# mainboard.net
KiCad netlist of a schematic drawn in Altium Designer
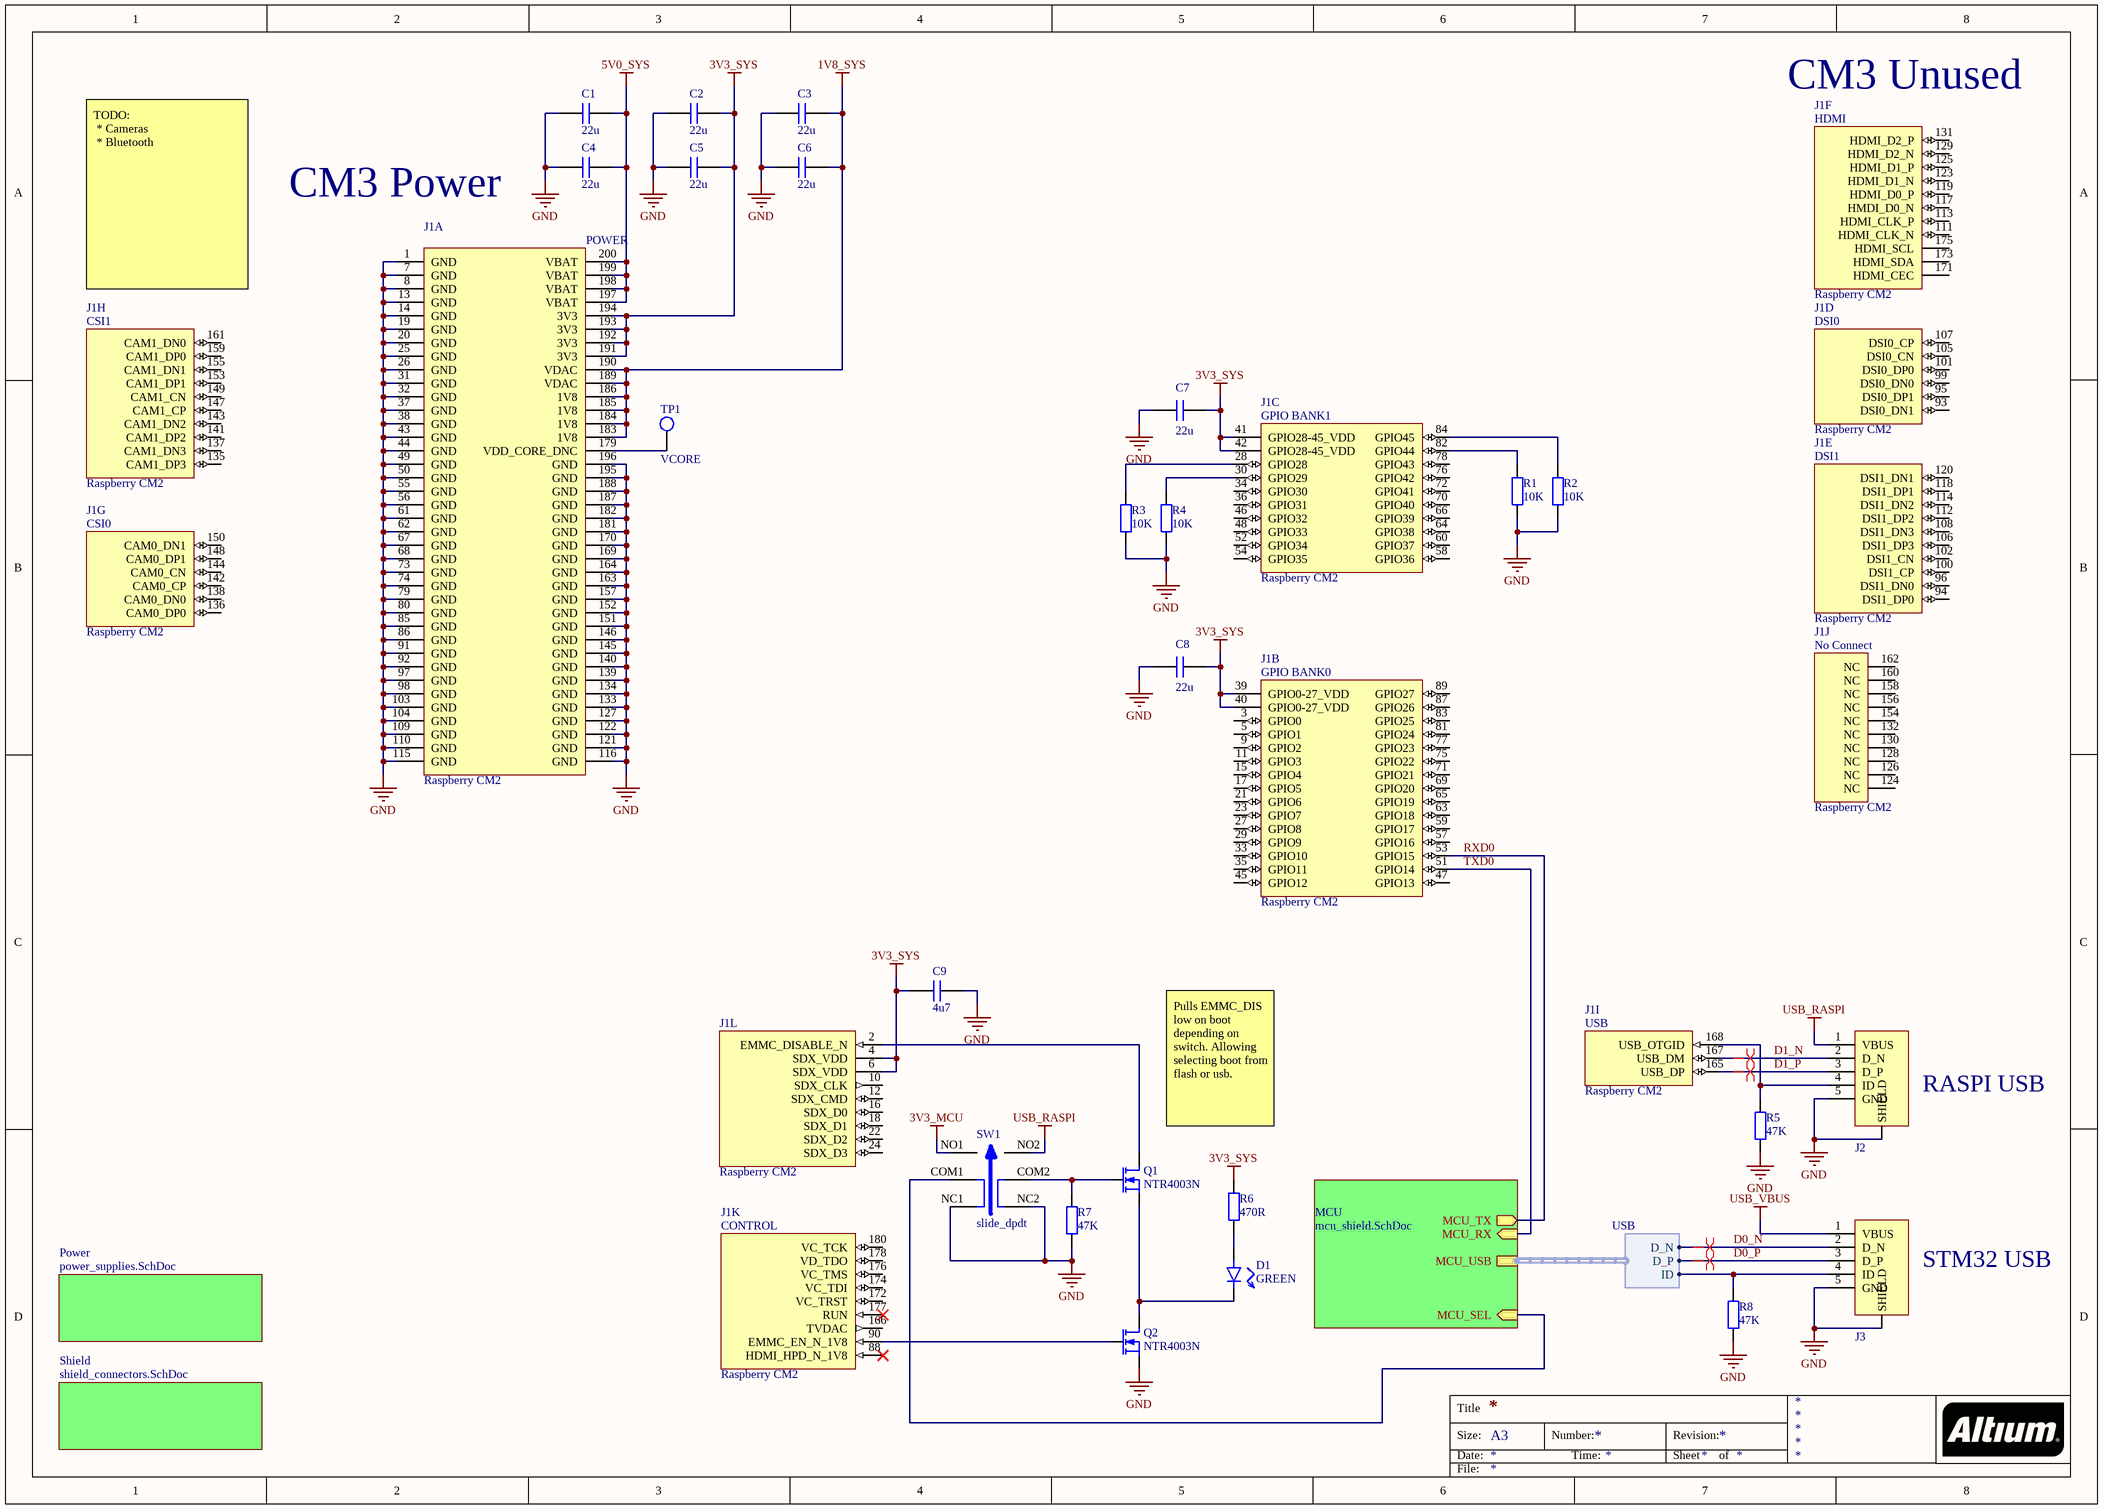
[diagram p0: mainboard.SchDoc]

(export (version "E")
  (design (tool "Eeschema 10.0.6"))
  (components
    (comp (ref "C1")
      (value "22u")
      (footprint "CAPC2012X11N")
      (description "Capacitor")
      (fields (field (name "Comment") "cap"))
      (libsource (lib "lib_passives") (part "cap"))
    )
    (comp (ref "C2")
      (value "22u")
      (footprint "CAPC2012X11N")
      (description "Capacitor")
      (fields (field (name "Comment") "cap"))
      (libsource (lib "lib_passives") (part "cap"))
    )
    (comp (ref "C3")
      (value "22u")
      (footprint "CAPC2012X11N")
      (description "Capacitor")
      (fields (field (name "Comment") "cap"))
      (libsource (lib "lib_passives") (part "cap"))
    )
    (comp (ref "C4")
      (value "22u")
      (footprint "CAPC2012X11N")
      (description "Capacitor")
      (fields (field (name "Comment") "cap"))
      (libsource (lib "lib_passives") (part "cap"))
    )
    (comp (ref "C5")
      (value "22u")
      (footprint "CAPC2012X11N")
      (description "Capacitor")
      (fields (field (name "Comment") "cap"))
      (libsource (lib "lib_passives") (part "cap"))
    )
    (comp (ref "C6")
      (value "22u")
      (footprint "CAPC2012X11N")
      (description "Capacitor")
      (fields (field (name "Comment") "cap"))
      (libsource (lib "lib_passives") (part "cap"))
    )
    (comp (ref "C7")
      (value "22u")
      (footprint "CAPC2012X11N")
      (description "Capacitor")
      (fields (field (name "Comment") "cap"))
      (libsource (lib "lib_passives") (part "cap"))
    )
    (comp (ref "C8")
      (value "22u")
      (footprint "CAPC2012X11N")
      (description "Capacitor")
      (fields (field (name "Comment") "cap"))
      (libsource (lib "lib_passives") (part "cap"))
    )
    (comp (ref "C9")
      (value "4u7")
      (footprint "CAPC1608X08N")
      (description "Capacitor")
      (fields (field (name "Comment") "cap"))
      (libsource (lib "lib_passives") (part "cap"))
    )
    (comp (ref "D1")
      (value "GREEN")
      (footprint "CAPCP1005X06N")
      (description "LED")
      (fields (field (name "Comment") "led"))
      (libsource (lib "lib_actives") (part "led"))
    )
    (comp (ref "J1")
      (value "Raspberry CM2")
      (footprint "raspi_cm3")
      (libsource (lib "lib_raspberry") (part "raspicm2"))
    )
    (comp (ref "J2")
      (value "usb_micro")
      (footprint "usb_micro_10118192-0001LF")
      (description "Micro USB Receptacle")
      (libsource (lib "lib_connectors") (part "usb_micro"))
    )
    (comp (ref "J3")
      (value "usb_micro")
      (footprint "usb_micro_10118192-0001LF")
      (description "Micro USB Receptacle")
      (libsource (lib "lib_connectors") (part "usb_micro"))
    )
    (comp (ref "Q1")
      (value "NTR4003N")
      (footprint "SOT95P235X100-3N")
      (description "N-channel Mosfet")
      (libsource (lib "lib_onsemi") (part "ntr4003n"))
    )
    (comp (ref "Q2")
      (value "NTR4003N")
      (footprint "SOT95P235X100-3N")
      (description "N-channel Mosfet")
      (libsource (lib "lib_onsemi") (part "ntr4003n"))
    )
    (comp (ref "R1")
      (value "10K")
      (footprint "RESC1005X04N")
      (description "Resistor")
      (fields (field (name "Comment") "res"))
      (libsource (lib "lib_passives") (part "res"))
    )
    (comp (ref "R2")
      (value "10K")
      (footprint "RESC1005X04N")
      (description "Resistor")
      (fields (field (name "Comment") "res"))
      (libsource (lib "lib_passives") (part "res"))
    )
    (comp (ref "R3")
      (value "10K")
      (footprint "RESC1005X04N")
      (description "Resistor")
      (fields (field (name "Comment") "res"))
      (libsource (lib "lib_passives") (part "res"))
    )
    (comp (ref "R4")
      (value "10K")
      (footprint "RESC1005X04N")
      (description "Resistor")
      (fields (field (name "Comment") "res"))
      (libsource (lib "lib_passives") (part "res"))
    )
    (comp (ref "R5")
      (value "47K")
      (footprint "RESC1005X04N")
      (description "Resistor")
      (fields (field (name "Comment") "res"))
      (libsource (lib "lib_passives") (part "res"))
    )
    (comp (ref "R6")
      (value "470R")
      (footprint "RESC1005X04N")
      (description "Resistor")
      (fields (field (name "Comment") "res"))
      (libsource (lib "lib_passives") (part "res"))
    )
    (comp (ref "R7")
      (value "47K")
      (footprint "RESC1005X04N")
      (description "Resistor")
      (fields (field (name "Comment") "res"))
      (libsource (lib "") (part "res_1"))
    )
    (comp (ref "R8")
      (value "47K")
      (footprint "RESC1005X04N")
      (description "Resistor")
      (fields (field (name "Comment") "res"))
      (libsource (lib "lib_passives") (part "res"))
    )
    (comp (ref "SW1")
      (value "slide_dpdt")
      (footprint "JS202011SCQN")
      (description "DPDT")
      (libsource (lib "lib_switches") (part "slide_dpdt"))
    )
    (comp (ref "TP1")
      (value "VCORE")
      (footprint "testpoint_smd")
      (description "Test point")
      (libsource (lib "lib_passives") (part "testpoint"))
    )
  )
  (nets
    (net (code "2") (name "/D0_N") (class "Default")
      (node (ref "J3") (pin "2") (pinfunction "D_N_2") (pintype "passive"))
    )
    (net (code "3") (name "/D0_P") (class "Default")
      (node (ref "J3") (pin "3") (pinfunction "D_P_3") (pintype "passive"))
    )
    (net (code "4") (name "/D1_N") (class "Default")
      (node (ref "J1") (pin "167") (pinfunction "USB_DM_167") (pintype "bidirectional"))
      (node (ref "J2") (pin "2") (pinfunction "D_N_2") (pintype "passive"))
    )
    (net (code "5") (name "/D1_P") (class "Default")
      (node (ref "J1") (pin "165") (pinfunction "USB_DP_165") (pintype "bidirectional"))
      (node (ref "J2") (pin "3") (pinfunction "D_P_3") (pintype "passive"))
    )
    (net (code "6") (name "/MCU_SEL") (class "Default")
      (node (ref "SW1") (pin "COM1") (pinfunction "COM1_COM1") (pintype "passive"))
    )
    (net (code "7") (name "/RXD0") (class "Default")
      (node (ref "J1") (pin "53") (pinfunction "GPIO15_53") (pintype "bidirectional"))
    )
    (net (code "8") (name "/TXD0") (class "Default")
      (node (ref "J1") (pin "51") (pinfunction "GPIO14_51") (pintype "bidirectional"))
    )
    (net (code "10") (name "1V8_SYS") (class "Default")
      (node (ref "C3") (pin "1") (pinfunction "1_1") (pintype "passive"))
      (node (ref "C6") (pin "1") (pinfunction "1_1") (pintype "passive"))
      (node (ref "J1") (pin "183") (pinfunction "1V8_183") (pintype "power_in"))
      (node (ref "J1") (pin "184") (pinfunction "1V8_184") (pintype "power_in"))
      (node (ref "J1") (pin "185") (pinfunction "1V8_185") (pintype "power_in"))
      (node (ref "J1") (pin "186") (pinfunction "1V8_186") (pintype "power_in"))
      (node (ref "J1") (pin "189") (pinfunction "VDAC_189") (pintype "power_in"))
      (node (ref "J1") (pin "190") (pinfunction "VDAC_190") (pintype "power_in"))
    )
    (net (code "11") (name "3V3_MCU") (class "Default")
      (node (ref "SW1") (pin "NO1") (pinfunction "NO1_NO1") (pintype "passive"))
    )
    (net (code "12") (name "3V3_SYS") (class "Default")
      (node (ref "C2") (pin "1") (pinfunction "1_1") (pintype "passive"))
      (node (ref "C5") (pin "1") (pinfunction "1_1") (pintype "passive"))
      (node (ref "C7") (pin "2") (pinfunction "2_2") (pintype "passive"))
      (node (ref "C8") (pin "2") (pinfunction "2_2") (pintype "passive"))
      (node (ref "C9") (pin "2") (pinfunction "2_2") (pintype "passive"))
      (node (ref "J1") (pin "191") (pinfunction "3V3_191") (pintype "power_in"))
      (node (ref "J1") (pin "192") (pinfunction "3V3_192") (pintype "power_in"))
      (node (ref "J1") (pin "193") (pinfunction "3V3_193") (pintype "power_in"))
      (node (ref "J1") (pin "194") (pinfunction "3V3_194") (pintype "power_in"))
      (node (ref "J1") (pin "39") (pinfunction "GPIO0-27_VDD_39") (pintype "power_in"))
      (node (ref "J1") (pin "4") (pinfunction "SDX_VDD_4") (pintype "power_in"))
      (node (ref "J1") (pin "40") (pinfunction "GPIO0-27_VDD_40") (pintype "power_in"))
      (node (ref "J1") (pin "41") (pinfunction "GPIO28-45_VDD_41") (pintype "power_in"))
      (node (ref "J1") (pin "42") (pinfunction "GPIO28-45_VDD_42") (pintype "power_in"))
      (node (ref "J1") (pin "6") (pinfunction "SDX_VDD_6") (pintype "power_in"))
      (node (ref "R6") (pin "2") (pinfunction "2_2") (pintype "passive"))
    )
    (net (code "13") (name "5V0_SYS") (class "Default")
      (node (ref "C1") (pin "1") (pinfunction "1_1") (pintype "passive"))
      (node (ref "C4") (pin "1") (pinfunction "1_1") (pintype "passive"))
      (node (ref "J1") (pin "197") (pinfunction "VBAT_197") (pintype "power_in"))
      (node (ref "J1") (pin "198") (pinfunction "VBAT_198") (pintype "power_in"))
      (node (ref "J1") (pin "199") (pinfunction "VBAT_199") (pintype "power_in"))
      (node (ref "J1") (pin "200") (pinfunction "VBAT_200") (pintype "power_in"))
    )
    (net (code "14") (name "GND") (class "Default")
      (node (ref "C1") (pin "2") (pinfunction "2_2") (pintype "passive"))
      (node (ref "C2") (pin "2") (pinfunction "2_2") (pintype "passive"))
      (node (ref "C3") (pin "2") (pinfunction "2_2") (pintype "passive"))
      (node (ref "C4") (pin "2") (pinfunction "2_2") (pintype "passive"))
      (node (ref "C5") (pin "2") (pinfunction "2_2") (pintype "passive"))
      (node (ref "C6") (pin "2") (pinfunction "2_2") (pintype "passive"))
      (node (ref "C7") (pin "1") (pinfunction "1_1") (pintype "passive"))
      (node (ref "C8") (pin "1") (pinfunction "1_1") (pintype "passive"))
      (node (ref "C9") (pin "1") (pinfunction "1_1") (pintype "passive"))
      (node (ref "J1") (pin "1") (pinfunction "GND_1") (pintype "power_in"))
      (node (ref "J1") (pin "103") (pinfunction "GND_103") (pintype "power_in"))
      (node (ref "J1") (pin "104") (pinfunction "GND_104") (pintype "power_in"))
      (node (ref "J1") (pin "109") (pinfunction "GND_109") (pintype "power_in"))
      (node (ref "J1") (pin "110") (pinfunction "GND_110") (pintype "power_in"))
      (node (ref "J1") (pin "115") (pinfunction "GND_115") (pintype "power_in"))
      (node (ref "J1") (pin "116") (pinfunction "GND_116") (pintype "power_in"))
      (node (ref "J1") (pin "121") (pinfunction "GND_121") (pintype "power_in"))
      (node (ref "J1") (pin "122") (pinfunction "GND_122") (pintype "power_in"))
      (node (ref "J1") (pin "127") (pinfunction "GND_127") (pintype "power_in"))
      (node (ref "J1") (pin "13") (pinfunction "GND_13") (pintype "power_in"))
      (node (ref "J1") (pin "133") (pinfunction "GND_133") (pintype "power_in"))
      (node (ref "J1") (pin "134") (pinfunction "GND_134") (pintype "power_in"))
      (node (ref "J1") (pin "139") (pinfunction "GND_139") (pintype "power_in"))
      (node (ref "J1") (pin "14") (pinfunction "GND_14") (pintype "power_in"))
      (node (ref "J1") (pin "140") (pinfunction "GND_140") (pintype "power_in"))
      (node (ref "J1") (pin "145") (pinfunction "GND_145") (pintype "power_in"))
      (node (ref "J1") (pin "146") (pinfunction "GND_146") (pintype "power_in"))
      (node (ref "J1") (pin "151") (pinfunction "GND_151") (pintype "power_in"))
      (node (ref "J1") (pin "152") (pinfunction "GND_152") (pintype "power_in"))
      (node (ref "J1") (pin "157") (pinfunction "GND_157") (pintype "power_in"))
      (node (ref "J1") (pin "163") (pinfunction "GND_163") (pintype "power_in"))
      (node (ref "J1") (pin "164") (pinfunction "GND_164") (pintype "power_in"))
      (node (ref "J1") (pin "169") (pinfunction "GND_169") (pintype "power_in"))
      (node (ref "J1") (pin "170") (pinfunction "GND_170") (pintype "power_in"))
      (node (ref "J1") (pin "181") (pinfunction "GND_181") (pintype "power_in"))
      (node (ref "J1") (pin "182") (pinfunction "GND_182") (pintype "power_in"))
      (node (ref "J1") (pin "187") (pinfunction "GND_187") (pintype "power_in"))
      (node (ref "J1") (pin "188") (pinfunction "GND_188") (pintype "power_in"))
      (node (ref "J1") (pin "19") (pinfunction "GND_19") (pintype "power_in"))
      (node (ref "J1") (pin "195") (pinfunction "GND_195") (pintype "power_in"))
      (node (ref "J1") (pin "196") (pinfunction "GND_196") (pintype "power_in"))
      (node (ref "J1") (pin "20") (pinfunction "GND_20") (pintype "power_in"))
      (node (ref "J1") (pin "25") (pinfunction "GND_25") (pintype "power_in"))
      (node (ref "J1") (pin "26") (pinfunction "GND_26") (pintype "power_in"))
      (node (ref "J1") (pin "31") (pinfunction "GND_31") (pintype "power_in"))
      (node (ref "J1") (pin "32") (pinfunction "GND_32") (pintype "power_in"))
      (node (ref "J1") (pin "37") (pinfunction "GND_37") (pintype "power_in"))
      (node (ref "J1") (pin "38") (pinfunction "GND_38") (pintype "power_in"))
      (node (ref "J1") (pin "43") (pinfunction "GND_43") (pintype "power_in"))
      (node (ref "J1") (pin "44") (pinfunction "GND_44") (pintype "power_in"))
      (node (ref "J1") (pin "49") (pinfunction "GND_49") (pintype "power_in"))
      (node (ref "J1") (pin "50") (pinfunction "GND_50") (pintype "power_in"))
      (node (ref "J1") (pin "55") (pinfunction "GND_55") (pintype "power_in"))
      (node (ref "J1") (pin "56") (pinfunction "GND_56") (pintype "power_in"))
      (node (ref "J1") (pin "61") (pinfunction "GND_61") (pintype "power_in"))
      (node (ref "J1") (pin "62") (pinfunction "GND_62") (pintype "power_in"))
      (node (ref "J1") (pin "67") (pinfunction "GND_67") (pintype "power_in"))
      (node (ref "J1") (pin "68") (pinfunction "GND_68") (pintype "power_in"))
      (node (ref "J1") (pin "7") (pinfunction "GND_7") (pintype "power_in"))
      (node (ref "J1") (pin "73") (pinfunction "GND_73") (pintype "power_in"))
      (node (ref "J1") (pin "74") (pinfunction "GND_74") (pintype "power_in"))
      (node (ref "J1") (pin "79") (pinfunction "GND_79") (pintype "power_in"))
      (node (ref "J1") (pin "8") (pinfunction "GND_8") (pintype "power_in"))
      (node (ref "J1") (pin "80") (pinfunction "GND_80") (pintype "power_in"))
      (node (ref "J1") (pin "85") (pinfunction "GND_85") (pintype "power_in"))
      (node (ref "J1") (pin "86") (pinfunction "GND_86") (pintype "power_in"))
      (node (ref "J1") (pin "91") (pinfunction "GND_91") (pintype "power_in"))
      (node (ref "J1") (pin "92") (pinfunction "GND_92") (pintype "power_in"))
      (node (ref "J1") (pin "97") (pinfunction "GND_97") (pintype "power_in"))
      (node (ref "J1") (pin "98") (pinfunction "GND_98") (pintype "power_in"))
      (node (ref "J2") (pin "5") (pinfunction "GND_5") (pintype "passive"))
      (node (ref "J2") (pin "SHIELD") (pinfunction "SHIELD_SHIELD") (pintype "passive"))
      (node (ref "J3") (pin "5") (pinfunction "GND_5") (pintype "passive"))
      (node (ref "J3") (pin "SHIELD") (pinfunction "SHIELD_SHIELD") (pintype "passive"))
      (node (ref "Q2") (pin "S") (pinfunction "S_S") (pintype "passive"))
      (node (ref "R1") (pin "1") (pinfunction "1_1") (pintype "passive"))
      (node (ref "R2") (pin "1") (pinfunction "1_1") (pintype "passive"))
      (node (ref "R3") (pin "1") (pinfunction "1_1") (pintype "passive"))
      (node (ref "R4") (pin "1") (pinfunction "1_1") (pintype "passive"))
      (node (ref "R5") (pin "1") (pinfunction "1_1") (pintype "passive"))
      (node (ref "R7") (pin "2") (pinfunction "2_2") (pintype "passive"))
      (node (ref "R8") (pin "1") (pinfunction "1_1") (pintype "passive"))
      (node (ref "SW1") (pin "NC1") (pinfunction "NC1_NC1") (pintype "passive"))
      (node (ref "SW1") (pin "NC2") (pinfunction "NC2_NC2") (pintype "passive"))
    )
    (net (code "15") (name "Net-(D1-PadA)") (class "Default")
      (node (ref "D1") (pin "A") (pinfunction "A_A") (pintype "passive"))
      (node (ref "R6") (pin "1") (pinfunction "1_1") (pintype "passive"))
    )
    (net (code "16") (name "Net-(D1-PadC)") (class "Default")
      (node (ref "D1") (pin "C") (pinfunction "C_C") (pintype "passive"))
      (node (ref "Q1") (pin "S") (pinfunction "S_S") (pintype "passive"))
      (node (ref "Q2") (pin "D") (pinfunction "D_D") (pintype "passive"))
    )
    (net (code "17") (name "Net-(J1A-VDD_CORE_DNC)") (class "Default")
      (node (ref "J1") (pin "179") (pinfunction "VDD_CORE_DNC_179") (pintype "power_in"))
      (node (ref "TP1") (pin "1") (pinfunction "1_1") (pintype "passive"))
    )
    (net (code "18") (name "Net-(J1C-GPIO28)") (class "Default")
      (node (ref "J1") (pin "28") (pinfunction "GPIO28_28") (pintype "bidirectional"))
      (node (ref "R3") (pin "2") (pinfunction "2_2") (pintype "passive"))
    )
    (net (code "19") (name "Net-(J1C-GPIO29)") (class "Default")
      (node (ref "J1") (pin "30") (pinfunction "GPIO29_30") (pintype "bidirectional"))
      (node (ref "R4") (pin "2") (pinfunction "2_2") (pintype "passive"))
    )
    (net (code "20") (name "Net-(J1C-GPIO44)") (class "Default")
      (node (ref "J1") (pin "82") (pinfunction "GPIO44_82") (pintype "bidirectional"))
      (node (ref "R1") (pin "2") (pinfunction "2_2") (pintype "passive"))
    )
    (net (code "21") (name "Net-(J1C-GPIO45)") (class "Default")
      (node (ref "J1") (pin "84") (pinfunction "GPIO45_84") (pintype "bidirectional"))
      (node (ref "R2") (pin "2") (pinfunction "2_2") (pintype "passive"))
    )
    (net (code "22") (name "Net-(J1I-USB_OTGID)") (class "Default")
      (node (ref "J1") (pin "168") (pinfunction "USB_OTGID_168") (pintype "input"))
      (node (ref "J2") (pin "4") (pinfunction "ID_4") (pintype "passive"))
      (node (ref "R5") (pin "2") (pinfunction "2_2") (pintype "passive"))
    )
    (net (code "23") (name "Net-(J1K-EMMC_EN_N_1V8)") (class "Default")
      (node (ref "J1") (pin "90") (pinfunction "EMMC_EN_N_1V8_90") (pintype "input"))
      (node (ref "Q2") (pin "G") (pinfunction "G_G") (pintype "passive"))
    )
    (net (code "24") (name "Net-(J1L-EMMC_DISABLE_N)") (class "Default")
      (node (ref "J1") (pin "2") (pinfunction "EMMC_DISABLE_N_2") (pintype "input"))
      (node (ref "Q1") (pin "D") (pinfunction "D_D") (pintype "passive"))
    )
    (net (code "25") (name "Net-(J3-ID)") (class "Default")
      (node (ref "J3") (pin "4") (pinfunction "ID_4") (pintype "passive"))
      (node (ref "R8") (pin "2") (pinfunction "2_2") (pintype "passive"))
    )
    (net (code "26") (name "Net-(Q1-PadG)") (class "Default")
      (node (ref "Q1") (pin "G") (pinfunction "G_G") (pintype "passive"))
      (node (ref "R7") (pin "1") (pinfunction "1_1") (pintype "passive"))
      (node (ref "SW1") (pin "COM2") (pinfunction "COM2_COM2") (pintype "passive"))
    )
    (net (code "27") (name "USB_RASPI") (class "Default")
      (node (ref "J2") (pin "1") (pinfunction "VBUS_1") (pintype "passive"))
      (node (ref "SW1") (pin "NO2") (pinfunction "NO2_NO2") (pintype "passive"))
    )
    (net (code "28") (name "USB_VBUS") (class "Default")
      (node (ref "J3") (pin "1") (pinfunction "VBUS_1") (pintype "passive"))
    )
    (net (code "29") (name "unconnected-(J1B-GPIO0-Pad3)") (class "Default")
      (node (ref "J1") (pin "3") (pinfunction "GPIO0_3") (pintype "bidirectional"))
    )
    (net (code "30") (name "unconnected-(J1B-GPIO1-Pad5)") (class "Default")
      (node (ref "J1") (pin "5") (pinfunction "GPIO1_5") (pintype "bidirectional"))
    )
    (net (code "31") (name "unconnected-(J1B-GPIO2-Pad9)") (class "Default")
      (node (ref "J1") (pin "9") (pinfunction "GPIO2_9") (pintype "bidirectional"))
    )
    (net (code "32") (name "unconnected-(J1B-GPIO3-Pad11)") (class "Default")
      (node (ref "J1") (pin "11") (pinfunction "GPIO3_11") (pintype "bidirectional"))
    )
    (net (code "33") (name "unconnected-(J1B-GPIO4-Pad15)") (class "Default")
      (node (ref "J1") (pin "15") (pinfunction "GPIO4_15") (pintype "bidirectional"))
    )
    (net (code "34") (name "unconnected-(J1B-GPIO5-Pad17)") (class "Default")
      (node (ref "J1") (pin "17") (pinfunction "GPIO5_17") (pintype "bidirectional"))
    )
    (net (code "35") (name "unconnected-(J1B-GPIO6-Pad21)") (class "Default")
      (node (ref "J1") (pin "21") (pinfunction "GPIO6_21") (pintype "bidirectional"))
    )
    (net (code "36") (name "unconnected-(J1B-GPIO7-Pad23)") (class "Default")
      (node (ref "J1") (pin "23") (pinfunction "GPIO7_23") (pintype "bidirectional"))
    )
    (net (code "37") (name "unconnected-(J1B-GPIO8-Pad27)") (class "Default")
      (node (ref "J1") (pin "27") (pinfunction "GPIO8_27") (pintype "bidirectional"))
    )
    (net (code "38") (name "unconnected-(J1B-GPIO9-Pad29)") (class "Default")
      (node (ref "J1") (pin "29") (pinfunction "GPIO9_29") (pintype "bidirectional"))
    )
    (net (code "39") (name "unconnected-(J1B-GPIO10-Pad33)") (class "Default")
      (node (ref "J1") (pin "33") (pinfunction "GPIO10_33") (pintype "bidirectional"))
    )
    (net (code "40") (name "unconnected-(J1B-GPIO11-Pad35)") (class "Default")
      (node (ref "J1") (pin "35") (pinfunction "GPIO11_35") (pintype "bidirectional"))
    )
    (net (code "41") (name "unconnected-(J1B-GPIO12-Pad45)") (class "Default")
      (node (ref "J1") (pin "45") (pinfunction "GPIO12_45") (pintype "bidirectional"))
    )
    (net (code "42") (name "unconnected-(J1B-GPIO13-Pad47)") (class "Default")
      (node (ref "J1") (pin "47") (pinfunction "GPIO13_47") (pintype "bidirectional"))
    )
    (net (code "43") (name "unconnected-(J1B-GPIO16-Pad57)") (class "Default")
      (node (ref "J1") (pin "57") (pinfunction "GPIO16_57") (pintype "bidirectional"))
    )
    (net (code "44") (name "unconnected-(J1B-GPIO17-Pad59)") (class "Default")
      (node (ref "J1") (pin "59") (pinfunction "GPIO17_59") (pintype "bidirectional"))
    )
    (net (code "45") (name "unconnected-(J1B-GPIO18-Pad63)") (class "Default")
      (node (ref "J1") (pin "63") (pinfunction "GPIO18_63") (pintype "bidirectional"))
    )
    (net (code "46") (name "unconnected-(J1B-GPIO19-Pad65)") (class "Default")
      (node (ref "J1") (pin "65") (pinfunction "GPIO19_65") (pintype "bidirectional"))
    )
    (net (code "47") (name "unconnected-(J1B-GPIO20-Pad69)") (class "Default")
      (node (ref "J1") (pin "69") (pinfunction "GPIO20_69") (pintype "bidirectional"))
    )
    (net (code "48") (name "unconnected-(J1B-GPIO21-Pad71)") (class "Default")
      (node (ref "J1") (pin "71") (pinfunction "GPIO21_71") (pintype "bidirectional"))
    )
    (net (code "49") (name "unconnected-(J1B-GPIO22-Pad75)") (class "Default")
      (node (ref "J1") (pin "75") (pinfunction "GPIO22_75") (pintype "bidirectional"))
    )
    (net (code "50") (name "unconnected-(J1B-GPIO23-Pad77)") (class "Default")
      (node (ref "J1") (pin "77") (pinfunction "GPIO23_77") (pintype "bidirectional"))
    )
    (net (code "51") (name "unconnected-(J1B-GPIO24-Pad81)") (class "Default")
      (node (ref "J1") (pin "81") (pinfunction "GPIO24_81") (pintype "bidirectional"))
    )
    (net (code "52") (name "unconnected-(J1B-GPIO25-Pad83)") (class "Default")
      (node (ref "J1") (pin "83") (pinfunction "GPIO25_83") (pintype "bidirectional"))
    )
    (net (code "53") (name "unconnected-(J1B-GPIO26-Pad87)") (class "Default")
      (node (ref "J1") (pin "87") (pinfunction "GPIO26_87") (pintype "bidirectional"))
    )
    (net (code "54") (name "unconnected-(J1B-GPIO27-Pad89)") (class "Default")
      (node (ref "J1") (pin "89") (pinfunction "GPIO27_89") (pintype "bidirectional"))
    )
    (net (code "55") (name "unconnected-(J1C-GPIO30-Pad34)") (class "Default")
      (node (ref "J1") (pin "34") (pinfunction "GPIO30_34") (pintype "bidirectional"))
    )
    (net (code "56") (name "unconnected-(J1C-GPIO31-Pad36)") (class "Default")
      (node (ref "J1") (pin "36") (pinfunction "GPIO31_36") (pintype "bidirectional"))
    )
    (net (code "57") (name "unconnected-(J1C-GPIO32-Pad46)") (class "Default")
      (node (ref "J1") (pin "46") (pinfunction "GPIO32_46") (pintype "bidirectional"))
    )
    (net (code "58") (name "unconnected-(J1C-GPIO33-Pad48)") (class "Default")
      (node (ref "J1") (pin "48") (pinfunction "GPIO33_48") (pintype "bidirectional"))
    )
    (net (code "59") (name "unconnected-(J1C-GPIO34-Pad52)") (class "Default")
      (node (ref "J1") (pin "52") (pinfunction "GPIO34_52") (pintype "bidirectional"))
    )
    (net (code "60") (name "unconnected-(J1C-GPIO35-Pad54)") (class "Default")
      (node (ref "J1") (pin "54") (pinfunction "GPIO35_54") (pintype "bidirectional"))
    )
    (net (code "61") (name "unconnected-(J1C-GPIO36-Pad58)") (class "Default")
      (node (ref "J1") (pin "58") (pinfunction "GPIO36_58") (pintype "bidirectional"))
    )
    (net (code "62") (name "unconnected-(J1C-GPIO37-Pad60)") (class "Default")
      (node (ref "J1") (pin "60") (pinfunction "GPIO37_60") (pintype "bidirectional"))
    )
    (net (code "63") (name "unconnected-(J1C-GPIO38-Pad64)") (class "Default")
      (node (ref "J1") (pin "64") (pinfunction "GPIO38_64") (pintype "bidirectional"))
    )
    (net (code "64") (name "unconnected-(J1C-GPIO39-Pad66)") (class "Default")
      (node (ref "J1") (pin "66") (pinfunction "GPIO39_66") (pintype "bidirectional"))
    )
    (net (code "65") (name "unconnected-(J1C-GPIO40-Pad70)") (class "Default")
      (node (ref "J1") (pin "70") (pinfunction "GPIO40_70") (pintype "bidirectional"))
    )
    (net (code "66") (name "unconnected-(J1C-GPIO41-Pad72)") (class "Default")
      (node (ref "J1") (pin "72") (pinfunction "GPIO41_72") (pintype "bidirectional"))
    )
    (net (code "67") (name "unconnected-(J1C-GPIO42-Pad76)") (class "Default")
      (node (ref "J1") (pin "76") (pinfunction "GPIO42_76") (pintype "bidirectional"))
    )
    (net (code "68") (name "unconnected-(J1C-GPIO43-Pad78)") (class "Default")
      (node (ref "J1") (pin "78") (pinfunction "GPIO43_78") (pintype "bidirectional"))
    )
    (net (code "69") (name "unconnected-(J1D-DSI0_CN-Pad105)") (class "Default")
      (node (ref "J1") (pin "105") (pinfunction "DSI0_CN_105") (pintype "bidirectional"))
    )
    (net (code "70") (name "unconnected-(J1D-DSI0_CP-Pad107)") (class "Default")
      (node (ref "J1") (pin "107") (pinfunction "DSI0_CP_107") (pintype "bidirectional"))
    )
    (net (code "71") (name "unconnected-(J1D-DSI0_DN0-Pad99)") (class "Default")
      (node (ref "J1") (pin "99") (pinfunction "DSI0_DN0_99") (pintype "bidirectional"))
    )
    (net (code "72") (name "unconnected-(J1D-DSI0_DN1-Pad93)") (class "Default")
      (node (ref "J1") (pin "93") (pinfunction "DSI0_DN1_93") (pintype "bidirectional"))
    )
    (net (code "73") (name "unconnected-(J1D-DSI0_DP0-Pad101)") (class "Default")
      (node (ref "J1") (pin "101") (pinfunction "DSI0_DP0_101") (pintype "bidirectional"))
    )
    (net (code "74") (name "unconnected-(J1D-DSI0_DP1-Pad95)") (class "Default")
      (node (ref "J1") (pin "95") (pinfunction "DSI0_DP1_95") (pintype "bidirectional"))
    )
    (net (code "75") (name "unconnected-(J1E-DSI1_CN-Pad102)") (class "Default")
      (node (ref "J1") (pin "102") (pinfunction "DSI1_CN_102") (pintype "bidirectional"))
    )
    (net (code "76") (name "unconnected-(J1E-DSI1_CP-Pad100)") (class "Default")
      (node (ref "J1") (pin "100") (pinfunction "DSI1_CP_100") (pintype "bidirectional"))
    )
    (net (code "77") (name "unconnected-(J1E-DSI1_DN0-Pad96)") (class "Default")
      (node (ref "J1") (pin "96") (pinfunction "DSI1_DN0_96") (pintype "bidirectional"))
    )
    (net (code "78") (name "unconnected-(J1E-DSI1_DN1-Pad120)") (class "Default")
      (node (ref "J1") (pin "120") (pinfunction "DSI1_DN1_120") (pintype "bidirectional"))
    )
    (net (code "79") (name "unconnected-(J1E-DSI1_DN2-Pad114)") (class "Default")
      (node (ref "J1") (pin "114") (pinfunction "DSI1_DN2_114") (pintype "bidirectional"))
    )
    (net (code "80") (name "unconnected-(J1E-DSI1_DN3-Pad108)") (class "Default")
      (node (ref "J1") (pin "108") (pinfunction "DSI1_DN3_108") (pintype "bidirectional"))
    )
    (net (code "81") (name "unconnected-(J1E-DSI1_DP0-Pad94)") (class "Default")
      (node (ref "J1") (pin "94") (pinfunction "DSI1_DP0_94") (pintype "bidirectional"))
    )
    (net (code "82") (name "unconnected-(J1E-DSI1_DP1-Pad118)") (class "Default")
      (node (ref "J1") (pin "118") (pinfunction "DSI1_DP1_118") (pintype "bidirectional"))
    )
    (net (code "83") (name "unconnected-(J1E-DSI1_DP2-Pad112)") (class "Default")
      (node (ref "J1") (pin "112") (pinfunction "DSI1_DP2_112") (pintype "bidirectional"))
    )
    (net (code "84") (name "unconnected-(J1E-DSI1_DP3-Pad106)") (class "Default")
      (node (ref "J1") (pin "106") (pinfunction "DSI1_DP3_106") (pintype "bidirectional"))
    )
    (net (code "85") (name "unconnected-(J1F-HDMI_CEC-Pad171)") (class "Default")
      (node (ref "J1") (pin "171") (pinfunction "HDMI_CEC_171") (pintype "open_collector"))
    )
    (net (code "86") (name "unconnected-(J1F-HDMI_CLK_N-Pad111)") (class "Default")
      (node (ref "J1") (pin "111") (pinfunction "HDMI_CLK_N_111") (pintype "bidirectional"))
    )
    (net (code "87") (name "unconnected-(J1F-HDMI_CLK_P-Pad113)") (class "Default")
      (node (ref "J1") (pin "113") (pinfunction "HDMI_CLK_P_113") (pintype "bidirectional"))
    )
    (net (code "88") (name "unconnected-(J1F-HDMI_D0_P-Pad119)") (class "Default")
      (node (ref "J1") (pin "119") (pinfunction "HDMI_D0_P_119") (pintype "bidirectional"))
    )
    (net (code "89") (name "unconnected-(J1F-HDMI_D1_N-Pad123)") (class "Default")
      (node (ref "J1") (pin "123") (pinfunction "HDMI_D1_N_123") (pintype "bidirectional"))
    )
    (net (code "90") (name "unconnected-(J1F-HDMI_D1_P-Pad125)") (class "Default")
      (node (ref "J1") (pin "125") (pinfunction "HDMI_D1_P_125") (pintype "bidirectional"))
    )
    (net (code "91") (name "unconnected-(J1F-HDMI_D2_N-Pad129)") (class "Default")
      (node (ref "J1") (pin "129") (pinfunction "HDMI_D2_N_129") (pintype "bidirectional"))
    )
    (net (code "92") (name "unconnected-(J1F-HDMI_D2_P-Pad131)") (class "Default")
      (node (ref "J1") (pin "131") (pinfunction "HDMI_D2_P_131") (pintype "bidirectional"))
    )
    (net (code "93") (name "unconnected-(J1F-HDMI_SCL-Pad175)") (class "Default")
      (node (ref "J1") (pin "175") (pinfunction "HDMI_SCL_175") (pintype "open_collector"))
    )
    (net (code "94") (name "unconnected-(J1F-HDMI_SDA-Pad173)") (class "Default")
      (node (ref "J1") (pin "173") (pinfunction "HDMI_SDA_173") (pintype "open_collector"))
    )
    (net (code "95") (name "unconnected-(J1F-HMDI_D0_N-Pad117)") (class "Default")
      (node (ref "J1") (pin "117") (pinfunction "HMDI_D0_N_117") (pintype "bidirectional"))
    )
    (net (code "96") (name "unconnected-(J1G-CAM0_CN-Pad144)") (class "Default")
      (node (ref "J1") (pin "144") (pinfunction "CAM0_CN_144") (pintype "bidirectional"))
    )
    (net (code "97") (name "unconnected-(J1G-CAM0_CP-Pad142)") (class "Default")
      (node (ref "J1") (pin "142") (pinfunction "CAM0_CP_142") (pintype "bidirectional"))
    )
    (net (code "98") (name "unconnected-(J1G-CAM0_DN0-Pad138)") (class "Default")
      (node (ref "J1") (pin "138") (pinfunction "CAM0_DN0_138") (pintype "bidirectional"))
    )
    (net (code "99") (name "unconnected-(J1G-CAM0_DN1-Pad150)") (class "Default")
      (node (ref "J1") (pin "150") (pinfunction "CAM0_DN1_150") (pintype "bidirectional"))
    )
    (net (code "100") (name "unconnected-(J1G-CAM0_DP0-Pad136)") (class "Default")
      (node (ref "J1") (pin "136") (pinfunction "CAM0_DP0_136") (pintype "bidirectional"))
    )
    (net (code "101") (name "unconnected-(J1G-CAM0_DP1-Pad148)") (class "Default")
      (node (ref "J1") (pin "148") (pinfunction "CAM0_DP1_148") (pintype "bidirectional"))
    )
    (net (code "102") (name "unconnected-(J1H-CAM1_CN-Pad149)") (class "Default")
      (node (ref "J1") (pin "149") (pinfunction "CAM1_CN_149") (pintype "bidirectional"))
    )
    (net (code "103") (name "unconnected-(J1H-CAM1_CP-Pad147)") (class "Default")
      (node (ref "J1") (pin "147") (pinfunction "CAM1_CP_147") (pintype "bidirectional"))
    )
    (net (code "104") (name "unconnected-(J1H-CAM1_DN0-Pad161)") (class "Default")
      (node (ref "J1") (pin "161") (pinfunction "CAM1_DN0_161") (pintype "bidirectional"))
    )
    (net (code "105") (name "unconnected-(J1H-CAM1_DN1-Pad155)") (class "Default")
      (node (ref "J1") (pin "155") (pinfunction "CAM1_DN1_155") (pintype "bidirectional"))
    )
    (net (code "106") (name "unconnected-(J1H-CAM1_DN2-Pad143)") (class "Default")
      (node (ref "J1") (pin "143") (pinfunction "CAM1_DN2_143") (pintype "bidirectional"))
    )
    (net (code "107") (name "unconnected-(J1H-CAM1_DN3-Pad137)") (class "Default")
      (node (ref "J1") (pin "137") (pinfunction "CAM1_DN3_137") (pintype "bidirectional"))
    )
    (net (code "108") (name "unconnected-(J1H-CAM1_DP0-Pad159)") (class "Default")
      (node (ref "J1") (pin "159") (pinfunction "CAM1_DP0_159") (pintype "bidirectional"))
    )
    (net (code "109") (name "unconnected-(J1H-CAM1_DP1-Pad153)") (class "Default")
      (node (ref "J1") (pin "153") (pinfunction "CAM1_DP1_153") (pintype "bidirectional"))
    )
    (net (code "110") (name "unconnected-(J1H-CAM1_DP2-Pad141)") (class "Default")
      (node (ref "J1") (pin "141") (pinfunction "CAM1_DP2_141") (pintype "bidirectional"))
    )
    (net (code "111") (name "unconnected-(J1H-CAM1_DP3-Pad135)") (class "Default")
      (node (ref "J1") (pin "135") (pinfunction "CAM1_DP3_135") (pintype "bidirectional"))
    )
    (net (code "112") (name "unconnected-(J1J-NC-Pad124)") (class "Default")
      (node (ref "J1") (pin "124") (pinfunction "NC_124") (pintype "passive"))
    )
    (net (code "113") (name "unconnected-(J1J-NC-Pad126)") (class "Default")
      (node (ref "J1") (pin "126") (pinfunction "NC_126") (pintype "passive"))
    )
    (net (code "114") (name "unconnected-(J1J-NC-Pad128)") (class "Default")
      (node (ref "J1") (pin "128") (pinfunction "NC_128") (pintype "passive"))
    )
    (net (code "115") (name "unconnected-(J1J-NC-Pad130)") (class "Default")
      (node (ref "J1") (pin "130") (pinfunction "NC_130") (pintype "passive"))
    )
    (net (code "116") (name "unconnected-(J1J-NC-Pad132)") (class "Default")
      (node (ref "J1") (pin "132") (pinfunction "NC_132") (pintype "passive"))
    )
    (net (code "117") (name "unconnected-(J1J-NC-Pad154)") (class "Default")
      (node (ref "J1") (pin "154") (pinfunction "NC_154") (pintype "passive"))
    )
    (net (code "118") (name "unconnected-(J1J-NC-Pad156)") (class "Default")
      (node (ref "J1") (pin "156") (pinfunction "NC_156") (pintype "passive"))
    )
    (net (code "119") (name "unconnected-(J1J-NC-Pad158)") (class "Default")
      (node (ref "J1") (pin "158") (pinfunction "NC_158") (pintype "passive"))
    )
    (net (code "120") (name "unconnected-(J1J-NC-Pad160)") (class "Default")
      (node (ref "J1") (pin "160") (pinfunction "NC_160") (pintype "passive"))
    )
    (net (code "121") (name "unconnected-(J1J-NC-Pad162)") (class "Default")
      (node (ref "J1") (pin "162") (pinfunction "NC_162") (pintype "passive"))
    )
    (net (code "122") (name "unconnected-(J1K-HDMI_HPD_N_1V8-Pad88)") (class "Default")
      (node (ref "J1") (pin "88") (pinfunction "HDMI_HPD_N_1V8_88") (pintype "input+no_connect"))
    )
    (net (code "123") (name "unconnected-(J1K-RUN-Pad177)") (class "Default")
      (node (ref "J1") (pin "177") (pinfunction "RUN_177") (pintype "input+no_connect"))
    )
    (net (code "124") (name "unconnected-(J1K-TVDAC-Pad166)") (class "Default")
      (node (ref "J1") (pin "166") (pinfunction "TVDAC_166") (pintype "output"))
    )
    (net (code "125") (name "unconnected-(J1K-VC_TCK-Pad180)") (class "Default")
      (node (ref "J1") (pin "180") (pinfunction "VC_TCK_180") (pintype "bidirectional"))
    )
    (net (code "126") (name "unconnected-(J1K-VC_TDI-Pad174)") (class "Default")
      (node (ref "J1") (pin "174") (pinfunction "VC_TDI_174") (pintype "bidirectional"))
    )
    (net (code "127") (name "unconnected-(J1K-VC_TMS-Pad176)") (class "Default")
      (node (ref "J1") (pin "176") (pinfunction "VC_TMS_176") (pintype "bidirectional"))
    )
    (net (code "128") (name "unconnected-(J1K-VC_TRST-Pad172)") (class "Default")
      (node (ref "J1") (pin "172") (pinfunction "VC_TRST_172") (pintype "bidirectional"))
    )
    (net (code "129") (name "unconnected-(J1K-VD_TDO-Pad178)") (class "Default")
      (node (ref "J1") (pin "178") (pinfunction "VD_TDO_178") (pintype "bidirectional"))
    )
    (net (code "130") (name "unconnected-(J1L-SDX_CLK-Pad10)") (class "Default")
      (node (ref "J1") (pin "10") (pinfunction "SDX_CLK_10") (pintype "output"))
    )
    (net (code "131") (name "unconnected-(J1L-SDX_CMD-Pad12)") (class "Default")
      (node (ref "J1") (pin "12") (pinfunction "SDX_CMD_12") (pintype "bidirectional"))
    )
    (net (code "132") (name "unconnected-(J1L-SDX_D0-Pad16)") (class "Default")
      (node (ref "J1") (pin "16") (pinfunction "SDX_D0_16") (pintype "bidirectional"))
    )
    (net (code "133") (name "unconnected-(J1L-SDX_D1-Pad18)") (class "Default")
      (node (ref "J1") (pin "18") (pinfunction "SDX_D1_18") (pintype "bidirectional"))
    )
    (net (code "134") (name "unconnected-(J1L-SDX_D2-Pad22)") (class "Default")
      (node (ref "J1") (pin "22") (pinfunction "SDX_D2_22") (pintype "bidirectional"))
    )
    (net (code "135") (name "unconnected-(J1L-SDX_D3-Pad24)") (class "Default")
      (node (ref "J1") (pin "24") (pinfunction "SDX_D3_24") (pintype "bidirectional"))
    )
  )
)
